# TWV.net
KiCad netlist of a schematic drawn in EAGLE
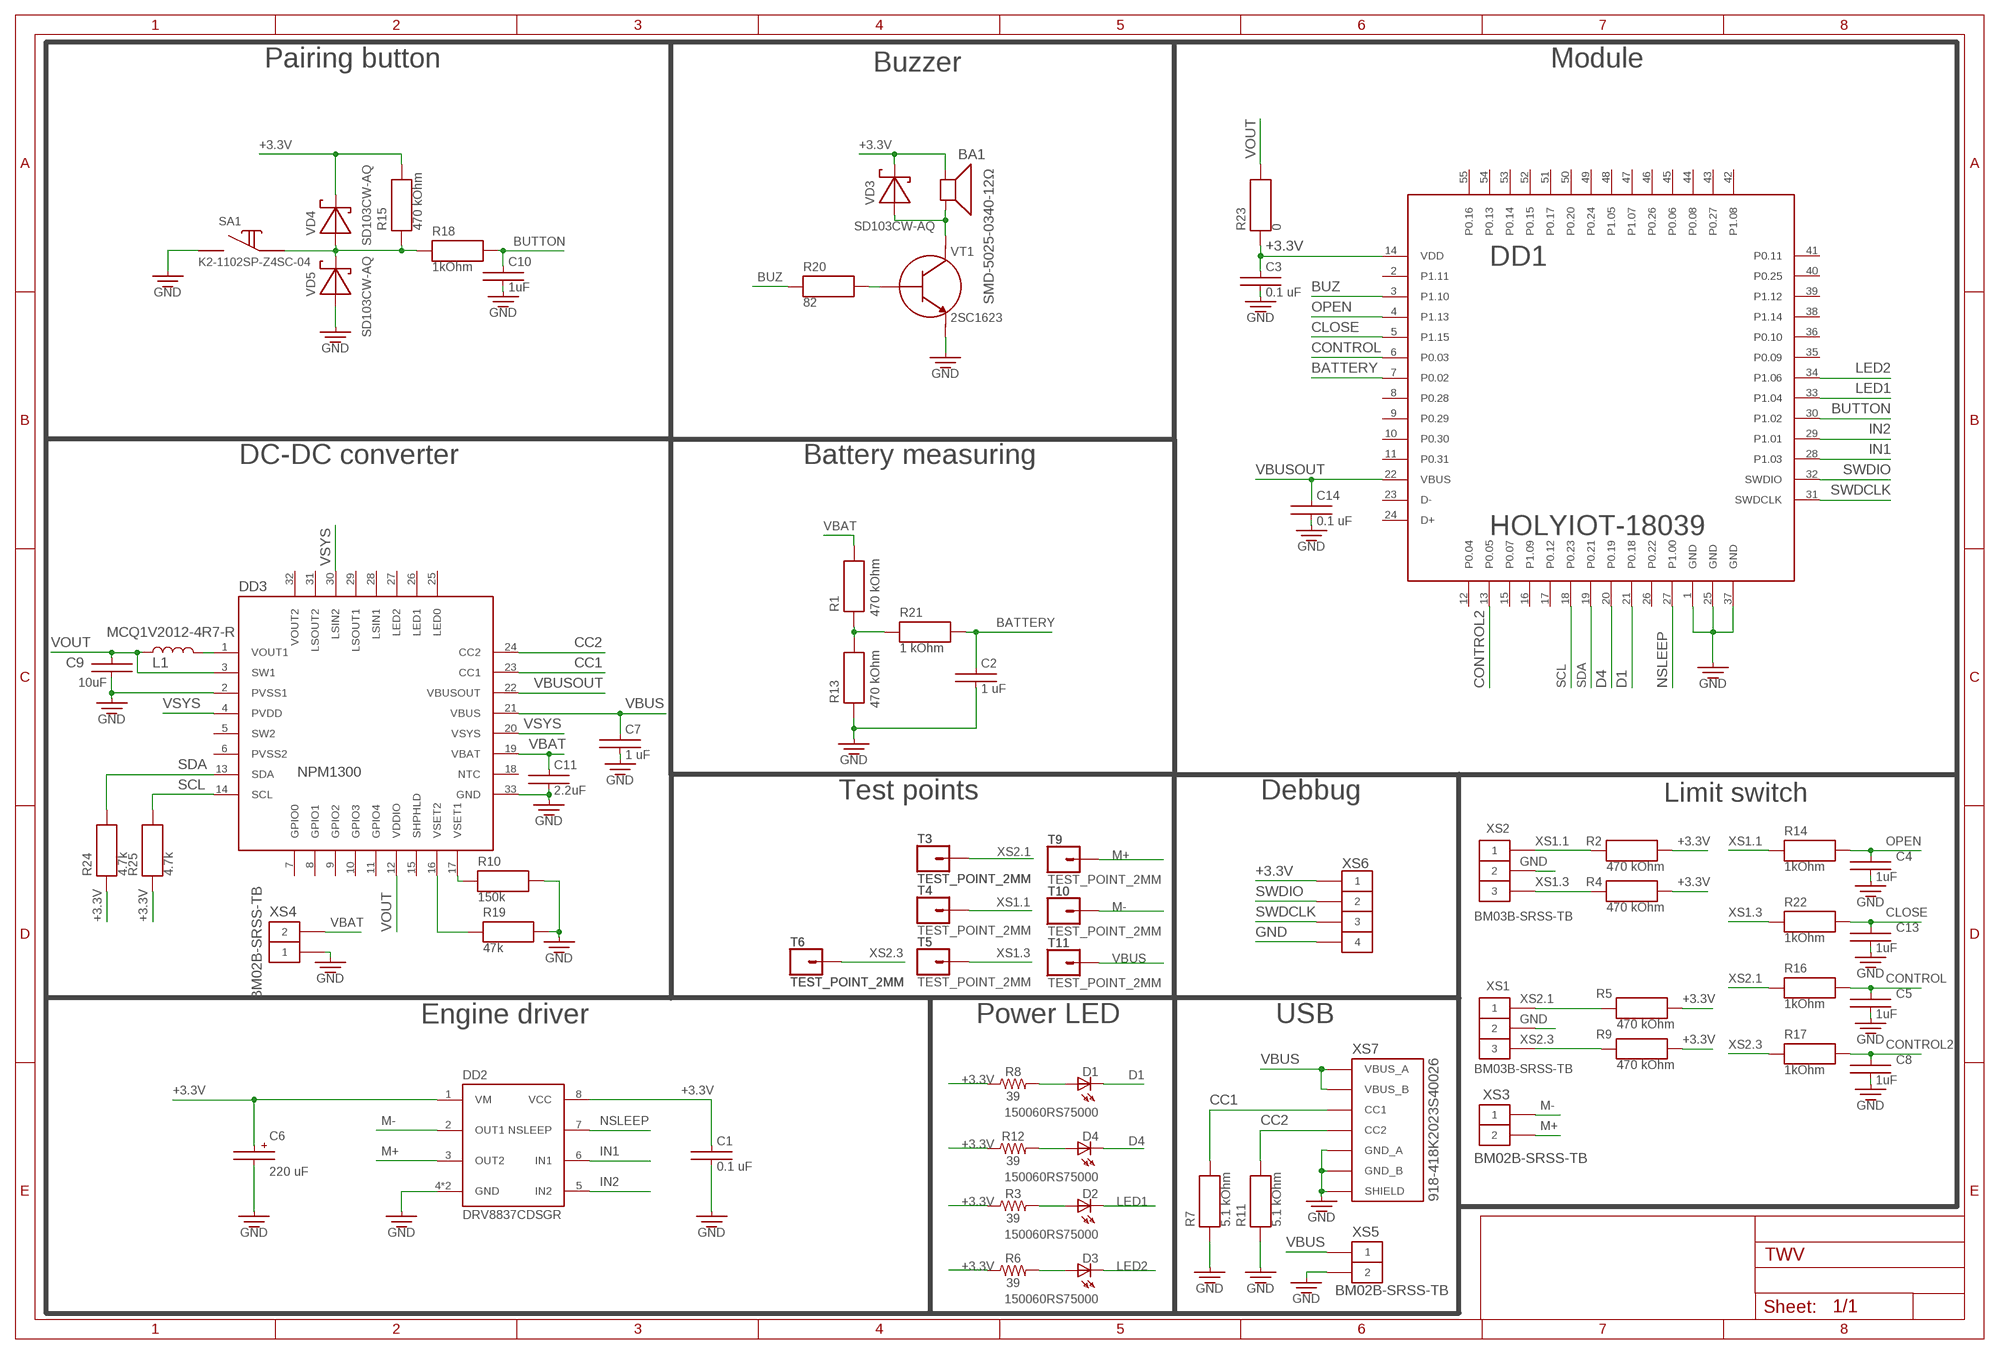
[diagram p0: schematic, sheet 1]

(export (version "E")
  (design (tool "Eeschema 10.0.6"))
  (components
    (comp (ref "BA1")
      (value "SMD-5025-0340-12Ω")
      (footprint "eagle-import:SMD-5025-0340-12Ω")
      (libsource (lib "eagle-import") (part "SMD-5025-0340-12Ω"))
    )
    (comp (ref "C1")
      (value "0.1 uF")
      (footprint "eagle-import:0603")
      (libsource (lib "eagle-import") (part "CAPACITOR-0603"))
    )
    (comp (ref "C2")
      (value "1 uF")
      (footprint "eagle-import:0603")
      (libsource (lib "eagle-import") (part "CAPACITOR-0603"))
    )
    (comp (ref "C3")
      (value "0.1 uF")
      (footprint "eagle-import:0603")
      (libsource (lib "eagle-import") (part "CAPACITOR-0603"))
    )
    (comp (ref "C4")
      (value "1uF")
      (footprint "eagle-import:0603")
      (libsource (lib "eagle-import") (part "CAPACITOR-0603"))
    )
    (comp (ref "C5")
      (value "1uF")
      (footprint "eagle-import:0603")
      (libsource (lib "eagle-import") (part "CAPACITOR-0603"))
    )
    (comp (ref "C6")
      (value "220 uF")
      (footprint "eagle-import:6.3X8")
      (libsource (lib "eagle-import") (part "ALUM_CAP_SMD-6.3X8"))
    )
    (comp (ref "C7")
      (value "1 uF")
      (footprint "eagle-import:0603")
      (libsource (lib "eagle-import") (part "CAPACITOR-0603"))
    )
    (comp (ref "C8")
      (value "1uF")
      (footprint "eagle-import:0603")
      (libsource (lib "eagle-import") (part "CAPACITOR-0603"))
    )
    (comp (ref "C9")
      (value "10uF")
      (footprint "eagle-import:0603")
      (libsource (lib "eagle-import") (part "CAPACITOR-0603"))
    )
    (comp (ref "C10")
      (value "1uF")
      (footprint "eagle-import:0603")
      (libsource (lib "eagle-import") (part "CAPACITOR-0603"))
    )
    (comp (ref "C11")
      (value "2.2uF")
      (footprint "eagle-import:0603")
      (libsource (lib "eagle-import") (part "CAPACITOR-0603"))
    )
    (comp (ref "C13")
      (value "1uF")
      (footprint "eagle-import:0603")
      (libsource (lib "eagle-import") (part "CAPACITOR-0603"))
    )
    (comp (ref "C14")
      (value "0.1 uF")
      (footprint "eagle-import:0603")
      (libsource (lib "eagle-import") (part "CAPACITOR-0603"))
    )
    (comp (ref "D1")
      (value "150060RS75000")
      (footprint "eagle-import:0603")
      (fields (field (name "MANUFACTURER") "Würth Elektronik"))
      (libsource (lib "eagle-import") (part "150060RS75000"))
    )
    (comp (ref "D2")
      (value "150060RS75000")
      (footprint "eagle-import:0603")
      (fields (field (name "MANUFACTURER") "Würth Elektronik"))
      (libsource (lib "eagle-import") (part "150060RS75000"))
    )
    (comp (ref "D3")
      (value "150060RS75000")
      (footprint "eagle-import:0603")
      (fields (field (name "MANUFACTURER") "Würth Elektronik"))
      (libsource (lib "eagle-import") (part "150060RS75000"))
    )
    (comp (ref "D4")
      (value "150060RS75000")
      (footprint "eagle-import:0603")
      (fields (field (name "MANUFACTURER") "Würth Elektronik"))
      (libsource (lib "eagle-import") (part "150060RS75000"))
    )
    (comp (ref "DD1")
      (value "HOLYIOT-18039")
      (footprint "eagle-import:HOLYIOT-18039")
      (libsource (lib "eagle-import") (part "HOLYIOT-18039"))
    )
    (comp (ref "DD2")
      (value "DRV8837CDSGR")
      (footprint "eagle-import:WSON-8")
      (libsource (lib "eagle-import") (part "DRV8837CDSGR"))
    )
    (comp (ref "DD3")
      (value "NPM1300")
      (footprint "eagle-import:QFN32-5X5MM")
      (libsource (lib "eagle-import") (part "NPM1300"))
    )
    (comp (ref "L1")
      (value "MCQ1V2012-4R7-R")
      (footprint "eagle-import:0805")
      (libsource (lib "eagle-import") (part "MCQ1V2012-4R7-R"))
    )
    (comp (ref "R1")
      (value "470 kOhm")
      (footprint "eagle-import:0603")
      (libsource (lib "eagle-import") (part "RESISTOR-0603"))
    )
    (comp (ref "R2")
      (value "470 kOhm")
      (footprint "eagle-import:0603")
      (libsource (lib "eagle-import") (part "RESISTOR-0603"))
    )
    (comp (ref "R3")
      (value "39")
      (footprint "eagle-import:RES0603")
      (fields (field (name "MANUFACTURER") "Yageo") (field (name "MPN") "RC0603JR-0739RL"))
      (libsource (lib "eagle-import") (part "RC0603JR-0739RL"))
    )
    (comp (ref "R4")
      (value "470 kOhm")
      (footprint "eagle-import:0603")
      (libsource (lib "eagle-import") (part "RESISTOR-0603"))
    )
    (comp (ref "R5")
      (value "470 kOhm")
      (footprint "eagle-import:0603")
      (libsource (lib "eagle-import") (part "RESISTOR-0603"))
    )
    (comp (ref "R6")
      (value "39")
      (footprint "eagle-import:RES0603")
      (fields (field (name "MANUFACTURER") "Yageo") (field (name "MPN") "RC0603JR-0739RL"))
      (libsource (lib "eagle-import") (part "RC0603JR-0739RL"))
    )
    (comp (ref "R7")
      (value "5.1 kOhm")
      (footprint "eagle-import:0603")
      (libsource (lib "eagle-import") (part "RESISTOR-0603"))
    )
    (comp (ref "R8")
      (value "39")
      (footprint "eagle-import:RES0603")
      (fields (field (name "MANUFACTURER") "Yageo") (field (name "MPN") "RC0603JR-0739RL"))
      (libsource (lib "eagle-import") (part "RC0603JR-0739RL"))
    )
    (comp (ref "R9")
      (value "470 kOhm")
      (footprint "eagle-import:0603")
      (libsource (lib "eagle-import") (part "RESISTOR-0603"))
    )
    (comp (ref "R10")
      (value "150k")
      (footprint "eagle-import:0603")
      (libsource (lib "eagle-import") (part "RESISTOR-0603"))
    )
    (comp (ref "R11")
      (value "5.1 kOhm")
      (footprint "eagle-import:0603")
      (libsource (lib "eagle-import") (part "RESISTOR-0603"))
    )
    (comp (ref "R12")
      (value "39")
      (footprint "eagle-import:RES0603")
      (fields (field (name "MANUFACTURER") "Yageo") (field (name "MPN") "RC0603JR-0739RL"))
      (libsource (lib "eagle-import") (part "RC0603JR-0739RL"))
    )
    (comp (ref "R13")
      (value "470 kOhm")
      (footprint "eagle-import:0603")
      (libsource (lib "eagle-import") (part "RESISTOR-0603"))
    )
    (comp (ref "R14")
      (value "1kOhm")
      (footprint "eagle-import:0603")
      (libsource (lib "eagle-import") (part "RESISTOR-0603"))
    )
    (comp (ref "R15")
      (value "470 kOhm")
      (footprint "eagle-import:0603")
      (libsource (lib "eagle-import") (part "RESISTOR-0603"))
    )
    (comp (ref "R16")
      (value "1kOhm")
      (footprint "eagle-import:0603")
      (libsource (lib "eagle-import") (part "RESISTOR-0603"))
    )
    (comp (ref "R17")
      (value "1kOhm")
      (footprint "eagle-import:0603")
      (libsource (lib "eagle-import") (part "RESISTOR-0603"))
    )
    (comp (ref "R18")
      (value "1kOhm")
      (footprint "eagle-import:0603")
      (libsource (lib "eagle-import") (part "RESISTOR-0603"))
    )
    (comp (ref "R19")
      (value "47k")
      (footprint "eagle-import:0603")
      (libsource (lib "eagle-import") (part "RESISTOR-0603"))
    )
    (comp (ref "R20")
      (value "82")
      (footprint "eagle-import:0603")
      (libsource (lib "eagle-import") (part "RESISTOR-0603"))
    )
    (comp (ref "R21")
      (value "1 kOhm")
      (footprint "eagle-import:0603")
      (libsource (lib "eagle-import") (part "RESISTOR-0603"))
    )
    (comp (ref "R22")
      (value "1kOhm")
      (footprint "eagle-import:0603")
      (libsource (lib "eagle-import") (part "RESISTOR-0603"))
    )
    (comp (ref "R23")
      (value "0")
      (footprint "eagle-import:0805")
      (libsource (lib "eagle-import") (part "RESISTOR-0805"))
    )
    (comp (ref "R24")
      (value "4.7k")
      (footprint "eagle-import:0603")
      (libsource (lib "eagle-import") (part "RESISTOR-0603"))
    )
    (comp (ref "R25")
      (value "4.7k")
      (footprint "eagle-import:0603")
      (libsource (lib "eagle-import") (part "RESISTOR-0603"))
    )
    (comp (ref "SA1")
      (value "K2-1102SP-Z4SC-04")
      (footprint "eagle-import:K2-1102SP-Z4SC-04")
      (libsource (lib "eagle-import") (part "K2-1102SP-Z4SC-04"))
    )
    (comp (ref "T3")
      (value "TEST_POINT_2MM")
      (footprint "eagle-import:TEST_POINT_2MM")
      (libsource (lib "eagle-import") (part "TEST_POINT_2MM"))
    )
    (comp (ref "T4")
      (value "TEST_POINT_2MM")
      (footprint "eagle-import:TEST_POINT_2MM")
      (libsource (lib "eagle-import") (part "TEST_POINT_2MM"))
    )
    (comp (ref "T5")
      (value "TEST_POINT_2MM")
      (footprint "eagle-import:TEST_POINT_2MM")
      (libsource (lib "eagle-import") (part "TEST_POINT_2MM"))
    )
    (comp (ref "T6")
      (value "TEST_POINT_2MM")
      (footprint "eagle-import:TEST_POINT_2MM")
      (libsource (lib "eagle-import") (part "TEST_POINT_2MM"))
    )
    (comp (ref "T9")
      (value "TEST_POINT_2MM")
      (footprint "eagle-import:TEST_POINT_2MM")
      (libsource (lib "eagle-import") (part "TEST_POINT_2MM"))
    )
    (comp (ref "T10")
      (value "TEST_POINT_2MM")
      (footprint "eagle-import:TEST_POINT_2MM")
      (libsource (lib "eagle-import") (part "TEST_POINT_2MM"))
    )
    (comp (ref "T11")
      (value "TEST_POINT_2MM")
      (footprint "eagle-import:TEST_POINT_2MM")
      (libsource (lib "eagle-import") (part "TEST_POINT_2MM"))
    )
    (comp (ref "VD3")
      (value "SD103CW-AQ")
      (footprint "eagle-import:SOD-123F")
      (libsource (lib "eagle-import") (part "SD103CW-AQ"))
    )
    (comp (ref "VD4")
      (value "SD103CW-AQ")
      (footprint "eagle-import:SOD-123F")
      (libsource (lib "eagle-import") (part "SD103CW-AQ"))
    )
    (comp (ref "VD5")
      (value "SD103CW-AQ")
      (footprint "eagle-import:SOD-123F")
      (libsource (lib "eagle-import") (part "SD103CW-AQ"))
    )
    (comp (ref "VT1")
      (value "2SC1623")
      (footprint "eagle-import:SOT-23")
      (libsource (lib "eagle-import") (part "2SC1623"))
    )
    (comp (ref "XS1")
      (value "BM03B-SRSS-TB")
      (footprint "eagle-import:BM03B-SRSS-TB")
      (libsource (lib "eagle-import") (part "BM03B-SRSS-TB"))
    )
    (comp (ref "XS2")
      (value "BM03B-SRSS-TB")
      (footprint "eagle-import:BM03B-SRSS-TB")
      (libsource (lib "eagle-import") (part "BM03B-SRSS-TB"))
    )
    (comp (ref "XS3")
      (value "BM02B-SRSS-TB")
      (footprint "eagle-import:BM02B-SRSS-TB")
      (libsource (lib "eagle-import") (part "BM02B-SRSS-TB"))
    )
    (comp (ref "XS4")
      (value "BM02B-SRSS-TB")
      (footprint "eagle-import:BM02B-SRSS-TB")
      (libsource (lib "eagle-import") (part "BM02B-SRSS-TB"))
    )
    (comp (ref "XS5")
      (value "BM02B-SRSS-TB")
      (footprint "eagle-import:BM02B-SRSS-TB")
      (libsource (lib "eagle-import") (part "BM02B-SRSS-TB"))
    )
    (comp (ref "XS6")
      (value "TH1X4-2.54MM")
      (footprint "eagle-import:TH1X4-2.54MM")
      (libsource (lib "eagle-import") (part "TH1X4-2.54MM"))
    )
    (comp (ref "XS7")
      (value "918-418K2023S40026")
      (footprint "eagle-import:918-418K2023S40026")
      (libsource (lib "eagle-import") (part "918-418K2023S40026"))
    )
  )
  (nets
    (net (code "1") (name "/+3.3V") (class "Default")
      (node (ref "BA1") (pin "+") (pinfunction "+_+") (pintype "bidirectional"))
      (node (ref "C1") (pin "1") (pinfunction "1_1") (pintype "bidirectional"))
      (node (ref "C3") (pin "1") (pinfunction "1_1") (pintype "bidirectional"))
      (node (ref "C6") (pin "+") (pinfunction "+_+") (pintype "bidirectional"))
      (node (ref "DD1") (pin "14") (pinfunction "VDD_14") (pintype "bidirectional"))
      (node (ref "DD2") (pin "1") (pinfunction "VM_1") (pintype "bidirectional"))
      (node (ref "DD2") (pin "8") (pinfunction "VCC_8") (pintype "bidirectional"))
      (node (ref "R12") (pin "1") (pinfunction "1_1") (pintype "passive"))
      (node (ref "R15") (pin "2") (pinfunction "2_2") (pintype "bidirectional"))
      (node (ref "R2") (pin "2") (pinfunction "2_2") (pintype "bidirectional"))
      (node (ref "R23") (pin "1") (pinfunction "1_1") (pintype "bidirectional"))
      (node (ref "R24") (pin "1") (pinfunction "1_1") (pintype "bidirectional"))
      (node (ref "R25") (pin "1") (pinfunction "1_1") (pintype "bidirectional"))
      (node (ref "R3") (pin "1") (pinfunction "1_1") (pintype "passive"))
      (node (ref "R4") (pin "2") (pinfunction "2_2") (pintype "bidirectional"))
      (node (ref "R5") (pin "2") (pinfunction "2_2") (pintype "bidirectional"))
      (node (ref "R6") (pin "1") (pinfunction "1_1") (pintype "passive"))
      (node (ref "R8") (pin "1") (pinfunction "1_1") (pintype "passive"))
      (node (ref "R9") (pin "2") (pinfunction "2_2") (pintype "bidirectional"))
      (node (ref "VD3") (pin "C") (pinfunction "C_C") (pintype "bidirectional"))
      (node (ref "VD4") (pin "C") (pinfunction "C_C") (pintype "bidirectional"))
      (node (ref "XS6") (pin "1") (pinfunction "1_1") (pintype "bidirectional"))
    )
    (net (code "2") (name "/BATTERY") (class "Default")
      (node (ref "C2") (pin "1") (pinfunction "1_1") (pintype "bidirectional"))
      (node (ref "DD1") (pin "7") (pinfunction "P0.02_7") (pintype "bidirectional"))
      (node (ref "R21") (pin "2") (pinfunction "2_2") (pintype "bidirectional"))
    )
    (net (code "3") (name "/BUTTON") (class "Default")
      (node (ref "C10") (pin "1") (pinfunction "1_1") (pintype "bidirectional"))
      (node (ref "DD1") (pin "30") (pinfunction "P1.02_30") (pintype "bidirectional"))
      (node (ref "R18") (pin "2") (pinfunction "2_2") (pintype "bidirectional"))
    )
    (net (code "4") (name "/BUZ") (class "Default")
      (node (ref "DD1") (pin "3") (pinfunction "P1.10_3") (pintype "bidirectional"))
      (node (ref "R20") (pin "1") (pinfunction "1_1") (pintype "bidirectional"))
    )
    (net (code "5") (name "/CC1") (class "Default")
      (node (ref "DD3") (pin "23") (pinfunction "CC1_23") (pintype "bidirectional"))
      (node (ref "R7") (pin "2") (pinfunction "2_2") (pintype "bidirectional"))
      (node (ref "XS7") (pin "A5") (pinfunction "CC1_A5") (pintype "bidirectional"))
    )
    (net (code "6") (name "/CC2") (class "Default")
      (node (ref "DD3") (pin "24") (pinfunction "CC2_24") (pintype "bidirectional"))
      (node (ref "R11") (pin "2") (pinfunction "2_2") (pintype "bidirectional"))
      (node (ref "XS7") (pin "B5") (pinfunction "CC2_B5") (pintype "bidirectional"))
    )
    (net (code "7") (name "/CLOSE") (class "Default")
      (node (ref "C13") (pin "1") (pinfunction "1_1") (pintype "bidirectional"))
      (node (ref "DD1") (pin "5") (pinfunction "P1.15_5") (pintype "bidirectional"))
      (node (ref "R22") (pin "2") (pinfunction "2_2") (pintype "bidirectional"))
    )
    (net (code "8") (name "/CONTROL") (class "Default")
      (node (ref "C5") (pin "1") (pinfunction "1_1") (pintype "bidirectional"))
      (node (ref "DD1") (pin "6") (pinfunction "P0.03_6") (pintype "bidirectional"))
      (node (ref "R16") (pin "2") (pinfunction "2_2") (pintype "bidirectional"))
    )
    (net (code "9") (name "/CONTROL2") (class "Default")
      (node (ref "C8") (pin "1") (pinfunction "1_1") (pintype "bidirectional"))
      (node (ref "DD1") (pin "13") (pinfunction "P0.05_13") (pintype "bidirectional"))
      (node (ref "R17") (pin "2") (pinfunction "2_2") (pintype "bidirectional"))
    )
    (net (code "10") (name "/D1") (class "Default")
      (node (ref "D1") (pin "C") (pinfunction "K_C") (pintype "passive"))
      (node (ref "DD1") (pin "21") (pinfunction "P0.18_21") (pintype "bidirectional"))
    )
    (net (code "11") (name "/D4") (class "Default")
      (node (ref "D4") (pin "C") (pinfunction "K_C") (pintype "passive"))
      (node (ref "DD1") (pin "20") (pinfunction "P0.19_20") (pintype "bidirectional"))
    )
    (net (code "12") (name "/IN1") (class "Default")
      (node (ref "DD1") (pin "28") (pinfunction "P1.03_28") (pintype "bidirectional"))
      (node (ref "DD2") (pin "6") (pinfunction "IN1_6") (pintype "bidirectional"))
    )
    (net (code "13") (name "/IN2") (class "Default")
      (node (ref "DD1") (pin "29") (pinfunction "P1.01_29") (pintype "bidirectional"))
      (node (ref "DD2") (pin "5") (pinfunction "IN2_5") (pintype "bidirectional"))
    )
    (net (code "14") (name "/LED1") (class "Default")
      (node (ref "D2") (pin "C") (pinfunction "K_C") (pintype "passive"))
      (node (ref "DD1") (pin "33") (pinfunction "P1.04_33") (pintype "bidirectional"))
    )
    (net (code "15") (name "/LED2") (class "Default")
      (node (ref "D3") (pin "C") (pinfunction "K_C") (pintype "passive"))
      (node (ref "DD1") (pin "34") (pinfunction "P1.06_34") (pintype "bidirectional"))
    )
    (net (code "16") (name "/M+") (class "Default")
      (node (ref "DD2") (pin "3") (pinfunction "OUT2_3") (pintype "bidirectional"))
      (node (ref "T9") (pin "1") (pinfunction "1_1") (pintype "passive"))
      (node (ref "XS3") (pin "2") (pinfunction "2_2") (pintype "bidirectional"))
    )
    (net (code "17") (name "/M-") (class "Default")
      (node (ref "DD2") (pin "2") (pinfunction "OUT1_2") (pintype "bidirectional"))
      (node (ref "T10") (pin "1") (pinfunction "1_1") (pintype "passive"))
      (node (ref "XS3") (pin "1") (pinfunction "1_1") (pintype "bidirectional"))
    )
    (net (code "18") (name "/NSLEEP") (class "Default")
      (node (ref "DD1") (pin "27") (pinfunction "P1.00_27") (pintype "bidirectional"))
      (node (ref "DD2") (pin "7") (pinfunction "NSLEEP_7") (pintype "bidirectional"))
    )
    (net (code "19") (name "/OPEN") (class "Default")
      (node (ref "C4") (pin "1") (pinfunction "1_1") (pintype "bidirectional"))
      (node (ref "DD1") (pin "4") (pinfunction "P1.13_4") (pintype "bidirectional"))
      (node (ref "R14") (pin "2") (pinfunction "2_2") (pintype "bidirectional"))
    )
    (net (code "20") (name "/SCL") (class "Default")
      (node (ref "DD1") (pin "18") (pinfunction "P0.23_18") (pintype "bidirectional"))
      (node (ref "DD3") (pin "14") (pinfunction "SCL_14") (pintype "bidirectional"))
      (node (ref "R25") (pin "2") (pinfunction "2_2") (pintype "bidirectional"))
    )
    (net (code "21") (name "/SDA") (class "Default")
      (node (ref "DD1") (pin "19") (pinfunction "P0.21_19") (pintype "bidirectional"))
      (node (ref "DD3") (pin "13") (pinfunction "SDA_13") (pintype "bidirectional"))
      (node (ref "R24") (pin "2") (pinfunction "2_2") (pintype "bidirectional"))
    )
    (net (code "22") (name "/SWDCLK") (class "Default")
      (node (ref "DD1") (pin "31") (pinfunction "SWDCLK_31") (pintype "bidirectional"))
      (node (ref "XS6") (pin "3") (pinfunction "3_3") (pintype "bidirectional"))
    )
    (net (code "23") (name "/SWDIO") (class "Default")
      (node (ref "DD1") (pin "32") (pinfunction "SWDIO_32") (pintype "bidirectional"))
      (node (ref "XS6") (pin "2") (pinfunction "2_2") (pintype "bidirectional"))
    )
    (net (code "24") (name "/VBAT") (class "Default")
      (node (ref "C11") (pin "1") (pinfunction "1_1") (pintype "bidirectional"))
      (node (ref "DD3") (pin "19") (pinfunction "VBAT_19") (pintype "bidirectional"))
      (node (ref "R1") (pin "2") (pinfunction "2_2") (pintype "bidirectional"))
      (node (ref "XS4") (pin "2") (pinfunction "2_2") (pintype "bidirectional"))
    )
    (net (code "25") (name "/VBUS") (class "Default")
      (node (ref "C7") (pin "1") (pinfunction "1_1") (pintype "bidirectional"))
      (node (ref "DD3") (pin "21") (pinfunction "VBUS_21") (pintype "bidirectional"))
      (node (ref "T11") (pin "1") (pinfunction "1_1") (pintype "passive"))
      (node (ref "XS5") (pin "1") (pinfunction "1_1") (pintype "bidirectional"))
      (node (ref "XS7") (pin "A9") (pinfunction "VBUS_A_A9") (pintype "bidirectional"))
      (node (ref "XS7") (pin "B9") (pinfunction "VBUS_B_B9") (pintype "bidirectional"))
    )
    (net (code "26") (name "/VBUSOUT") (class "Default")
      (node (ref "C14") (pin "1") (pinfunction "1_1") (pintype "bidirectional"))
      (node (ref "DD1") (pin "22") (pinfunction "VBUS_22") (pintype "bidirectional"))
      (node (ref "DD3") (pin "22") (pinfunction "VBUSOUT_22") (pintype "bidirectional"))
    )
    (net (code "27") (name "/VOUT") (class "Default")
      (node (ref "C9") (pin "1") (pinfunction "1_1") (pintype "bidirectional"))
      (node (ref "DD3") (pin "12") (pinfunction "VDDIO_12") (pintype "bidirectional"))
      (node (ref "DD3") (pin "3") (pinfunction "SW1_3") (pintype "bidirectional"))
      (node (ref "L1") (pin "P$1") (pinfunction "1_P$1") (pintype "bidirectional"))
      (node (ref "R23") (pin "2") (pinfunction "2_2") (pintype "bidirectional"))
    )
    (net (code "28") (name "/VSYS") (class "Default")
      (node (ref "DD3") (pin "20") (pinfunction "VSYS_20") (pintype "bidirectional"))
      (node (ref "DD3") (pin "30") (pinfunction "LSIN2_30") (pintype "bidirectional"))
      (node (ref "DD3") (pin "4") (pinfunction "PVDD_4") (pintype "bidirectional"))
    )
    (net (code "29") (name "/XS1.1") (class "Default")
      (node (ref "R14") (pin "1") (pinfunction "1_1") (pintype "bidirectional"))
      (node (ref "R2") (pin "1") (pinfunction "1_1") (pintype "bidirectional"))
      (node (ref "T4") (pin "1") (pinfunction "1_1") (pintype "passive"))
      (node (ref "XS2") (pin "1") (pinfunction "1_1") (pintype "bidirectional"))
    )
    (net (code "30") (name "/XS1.3") (class "Default")
      (node (ref "R22") (pin "1") (pinfunction "1_1") (pintype "bidirectional"))
      (node (ref "R4") (pin "1") (pinfunction "1_1") (pintype "bidirectional"))
      (node (ref "T5") (pin "1") (pinfunction "1_1") (pintype "passive"))
      (node (ref "XS2") (pin "3") (pinfunction "3_3") (pintype "bidirectional"))
    )
    (net (code "31") (name "/XS2.1") (class "Default")
      (node (ref "R16") (pin "1") (pinfunction "1_1") (pintype "bidirectional"))
      (node (ref "R5") (pin "1") (pinfunction "1_1") (pintype "bidirectional"))
      (node (ref "T3") (pin "1") (pinfunction "1_1") (pintype "passive"))
      (node (ref "XS1") (pin "1") (pinfunction "1_1") (pintype "bidirectional"))
    )
    (net (code "32") (name "/XS2.3") (class "Default")
      (node (ref "R17") (pin "1") (pinfunction "1_1") (pintype "bidirectional"))
      (node (ref "R9") (pin "1") (pinfunction "1_1") (pintype "bidirectional"))
      (node (ref "T6") (pin "1") (pinfunction "1_1") (pintype "passive"))
      (node (ref "XS1") (pin "3") (pinfunction "3_3") (pintype "bidirectional"))
    )
    (net (code "33") (name "GND") (class "Default")
      (node (ref "C1") (pin "2") (pinfunction "2_2") (pintype "bidirectional"))
      (node (ref "C10") (pin "2") (pinfunction "2_2") (pintype "bidirectional"))
      (node (ref "C11") (pin "2") (pinfunction "2_2") (pintype "bidirectional"))
      (node (ref "C13") (pin "2") (pinfunction "2_2") (pintype "bidirectional"))
      (node (ref "C14") (pin "2") (pinfunction "2_2") (pintype "bidirectional"))
      (node (ref "C2") (pin "2") (pinfunction "2_2") (pintype "bidirectional"))
      (node (ref "C3") (pin "2") (pinfunction "2_2") (pintype "bidirectional"))
      (node (ref "C4") (pin "2") (pinfunction "2_2") (pintype "bidirectional"))
      (node (ref "C5") (pin "2") (pinfunction "2_2") (pintype "bidirectional"))
      (node (ref "C6") (pin "-") (pinfunction "-_-") (pintype "bidirectional"))
      (node (ref "C7") (pin "2") (pinfunction "2_2") (pintype "bidirectional"))
      (node (ref "C8") (pin "2") (pinfunction "2_2") (pintype "bidirectional"))
      (node (ref "C9") (pin "2") (pinfunction "2_2") (pintype "bidirectional"))
      (node (ref "DD1") (pin "1") (pinfunction "GND_1") (pintype "bidirectional"))
      (node (ref "DD1") (pin "25") (pinfunction "GND_25") (pintype "bidirectional"))
      (node (ref "DD1") (pin "37") (pinfunction "GND_37") (pintype "bidirectional"))
      (node (ref "DD2") (pin "4") (pinfunction "GND_4") (pintype "bidirectional"))
      (node (ref "DD2") (pin "GND") (pinfunction "GND_GND") (pintype "bidirectional"))
      (node (ref "DD3") (pin "2") (pinfunction "PVSS1_2") (pintype "bidirectional"))
      (node (ref "DD3") (pin "33") (pinfunction "GND_33") (pintype "bidirectional"))
      (node (ref "R10") (pin "2") (pinfunction "2_2") (pintype "bidirectional"))
      (node (ref "R11") (pin "1") (pinfunction "1_1") (pintype "bidirectional"))
      (node (ref "R13") (pin "1") (pinfunction "1_1") (pintype "bidirectional"))
      (node (ref "R19") (pin "2") (pinfunction "2_2") (pintype "bidirectional"))
      (node (ref "R7") (pin "1") (pinfunction "1_1") (pintype "bidirectional"))
      (node (ref "SA1") (pin "1") (pinfunction "1_1") (pintype "bidirectional"))
      (node (ref "SA1") (pin "4") (pinfunction "1_4") (pintype "bidirectional"))
      (node (ref "VD5") (pin "A") (pinfunction "A_A") (pintype "bidirectional"))
      (node (ref "VT1") (pin "2") (pinfunction "E_2") (pintype "bidirectional"))
      (node (ref "XS1") (pin "2") (pinfunction "2_2") (pintype "bidirectional"))
      (node (ref "XS2") (pin "2") (pinfunction "2_2") (pintype "bidirectional"))
      (node (ref "XS4") (pin "1") (pinfunction "1_1") (pintype "bidirectional"))
      (node (ref "XS5") (pin "2") (pinfunction "2_2") (pintype "bidirectional"))
      (node (ref "XS6") (pin "4") (pinfunction "4_4") (pintype "bidirectional"))
      (node (ref "XS7") (pin "A12") (pinfunction "GND_A_A12") (pintype "bidirectional"))
      (node (ref "XS7") (pin "B12") (pinfunction "GND_B_B12") (pintype "bidirectional"))
      (node (ref "XS7") (pin "SH1") (pinfunction "SHIELD_SH1") (pintype "bidirectional"))
      (node (ref "XS7") (pin "SH2") (pinfunction "SHIELD_SH2") (pintype "bidirectional"))
      (node (ref "XS7") (pin "SH3") (pinfunction "SHIELD_SH3") (pintype "bidirectional"))
      (node (ref "XS7") (pin "SH4") (pinfunction "SHIELD_SH4") (pintype "bidirectional"))
    )
    (net (code "34") (name "Net-(D1-PadA)") (class "Default")
      (node (ref "D1") (pin "A") (pinfunction "A_A") (pintype "passive"))
      (node (ref "R8") (pin "2") (pinfunction "2_2") (pintype "passive"))
    )
    (net (code "35") (name "Net-(D2-PadA)") (class "Default")
      (node (ref "D2") (pin "A") (pinfunction "A_A") (pintype "passive"))
      (node (ref "R3") (pin "2") (pinfunction "2_2") (pintype "passive"))
    )
    (net (code "36") (name "Net-(D3-PadA)") (class "Default")
      (node (ref "D3") (pin "A") (pinfunction "A_A") (pintype "passive"))
      (node (ref "R6") (pin "2") (pinfunction "2_2") (pintype "passive"))
    )
    (net (code "37") (name "Net-(D4-PadA)") (class "Default")
      (node (ref "D4") (pin "A") (pinfunction "A_A") (pintype "passive"))
      (node (ref "R12") (pin "2") (pinfunction "2_2") (pintype "passive"))
    )
    (net (code "38") (name "Net-(DD3-VOUT1)") (class "Default")
      (node (ref "DD3") (pin "1") (pinfunction "VOUT1_1") (pintype "bidirectional"))
      (node (ref "L1") (pin "P$2") (pinfunction "2_P$2") (pintype "bidirectional"))
    )
    (net (code "39") (name "Net-(DD3-VSET1)") (class "Default")
      (node (ref "DD3") (pin "17") (pinfunction "VSET1_17") (pintype "bidirectional"))
      (node (ref "R10") (pin "1") (pinfunction "1_1") (pintype "bidirectional"))
    )
    (net (code "40") (name "Net-(DD3-VSET2)") (class "Default")
      (node (ref "DD3") (pin "16") (pinfunction "VSET2_16") (pintype "bidirectional"))
      (node (ref "R19") (pin "1") (pinfunction "1_1") (pintype "bidirectional"))
    )
    (net (code "41") (name "Net-(R1-Pad1)") (class "Default")
      (node (ref "R1") (pin "1") (pinfunction "1_1") (pintype "bidirectional"))
      (node (ref "R13") (pin "2") (pinfunction "2_2") (pintype "bidirectional"))
      (node (ref "R21") (pin "1") (pinfunction "1_1") (pintype "bidirectional"))
    )
    (net (code "42") (name "Net-(R15-Pad1)") (class "Default")
      (node (ref "R15") (pin "1") (pinfunction "1_1") (pintype "bidirectional"))
      (node (ref "R18") (pin "1") (pinfunction "1_1") (pintype "bidirectional"))
      (node (ref "SA1") (pin "2") (pinfunction "2_2") (pintype "bidirectional"))
      (node (ref "SA1") (pin "3") (pinfunction "2_3") (pintype "bidirectional"))
      (node (ref "VD4") (pin "A") (pinfunction "A_A") (pintype "bidirectional"))
      (node (ref "VD5") (pin "C") (pinfunction "C_C") (pintype "bidirectional"))
    )
    (net (code "43") (name "Net-(VT1-B)") (class "Default")
      (node (ref "R20") (pin "2") (pinfunction "2_2") (pintype "bidirectional"))
      (node (ref "VT1") (pin "1") (pinfunction "B_1") (pintype "bidirectional"))
    )
    (net (code "44") (name "Net-(VT1-C)") (class "Default")
      (node (ref "BA1") (pin "-") (pinfunction "-_-") (pintype "bidirectional"))
      (node (ref "VD3") (pin "A") (pinfunction "A_A") (pintype "bidirectional"))
      (node (ref "VT1") (pin "3") (pinfunction "C_3") (pintype "bidirectional"))
    )
    (net (code "45") (name "unconnected-(DD1-D+-Pad24)") (class "Default")
      (node (ref "DD1") (pin "24") (pinfunction "D+_24") (pintype "bidirectional"))
    )
    (net (code "46") (name "unconnected-(DD1-D--Pad23)") (class "Default")
      (node (ref "DD1") (pin "23") (pinfunction "D-_23") (pintype "bidirectional"))
    )
    (net (code "47") (name "unconnected-(DD1-P0.04-Pad12)") (class "Default")
      (node (ref "DD1") (pin "12") (pinfunction "P0.04_12") (pintype "bidirectional"))
    )
    (net (code "48") (name "unconnected-(DD1-P0.06-Pad45)") (class "Default")
      (node (ref "DD1") (pin "45") (pinfunction "P0.06_45") (pintype "bidirectional"))
    )
    (net (code "49") (name "unconnected-(DD1-P0.07-Pad15)") (class "Default")
      (node (ref "DD1") (pin "15") (pinfunction "P0.07_15") (pintype "bidirectional"))
    )
    (net (code "50") (name "unconnected-(DD1-P0.08-Pad44)") (class "Default")
      (node (ref "DD1") (pin "44") (pinfunction "P0.08_44") (pintype "bidirectional"))
    )
    (net (code "51") (name "unconnected-(DD1-P0.09-Pad35)") (class "Default")
      (node (ref "DD1") (pin "35") (pinfunction "P0.09_35") (pintype "bidirectional"))
    )
    (net (code "52") (name "unconnected-(DD1-P0.10-Pad36)") (class "Default")
      (node (ref "DD1") (pin "36") (pinfunction "P0.10_36") (pintype "bidirectional"))
    )
    (net (code "53") (name "unconnected-(DD1-P0.11-Pad41)") (class "Default")
      (node (ref "DD1") (pin "41") (pinfunction "P0.11_41") (pintype "bidirectional"))
    )
    (net (code "54") (name "unconnected-(DD1-P0.12-Pad17)") (class "Default")
      (node (ref "DD1") (pin "17") (pinfunction "P0.12_17") (pintype "bidirectional"))
    )
    (net (code "55") (name "unconnected-(DD1-P0.13-Pad54)") (class "Default")
      (node (ref "DD1") (pin "54") (pinfunction "P0.13_54") (pintype "bidirectional"))
    )
    (net (code "56") (name "unconnected-(DD1-P0.14-Pad53)") (class "Default")
      (node (ref "DD1") (pin "53") (pinfunction "P0.14_53") (pintype "bidirectional"))
    )
    (net (code "57") (name "unconnected-(DD1-P0.15-Pad52)") (class "Default")
      (node (ref "DD1") (pin "52") (pinfunction "P0.15_52") (pintype "bidirectional"))
    )
    (net (code "58") (name "unconnected-(DD1-P0.16-Pad55)") (class "Default")
      (node (ref "DD1") (pin "55") (pinfunction "P0.16_55") (pintype "bidirectional"))
    )
    (net (code "59") (name "unconnected-(DD1-P0.17-Pad51)") (class "Default")
      (node (ref "DD1") (pin "51") (pinfunction "P0.17_51") (pintype "bidirectional"))
    )
    (net (code "60") (name "unconnected-(DD1-P0.20-Pad50)") (class "Default")
      (node (ref "DD1") (pin "50") (pinfunction "P0.20_50") (pintype "bidirectional"))
    )
    (net (code "61") (name "unconnected-(DD1-P0.22-Pad26)") (class "Default")
      (node (ref "DD1") (pin "26") (pinfunction "P0.22_26") (pintype "bidirectional"))
    )
    (net (code "62") (name "unconnected-(DD1-P0.24-Pad49)") (class "Default")
      (node (ref "DD1") (pin "49") (pinfunction "P0.24_49") (pintype "bidirectional"))
    )
    (net (code "63") (name "unconnected-(DD1-P0.25-Pad40)") (class "Default")
      (node (ref "DD1") (pin "40") (pinfunction "P0.25_40") (pintype "bidirectional"))
    )
    (net (code "64") (name "unconnected-(DD1-P0.26-Pad46)") (class "Default")
      (node (ref "DD1") (pin "46") (pinfunction "P0.26_46") (pintype "bidirectional"))
    )
    (net (code "65") (name "unconnected-(DD1-P0.27-Pad43)") (class "Default")
      (node (ref "DD1") (pin "43") (pinfunction "P0.27_43") (pintype "bidirectional"))
    )
    (net (code "66") (name "unconnected-(DD1-P0.28-Pad8)") (class "Default")
      (node (ref "DD1") (pin "8") (pinfunction "P0.28_8") (pintype "bidirectional"))
    )
    (net (code "67") (name "unconnected-(DD1-P0.29-Pad9)") (class "Default")
      (node (ref "DD1") (pin "9") (pinfunction "P0.29_9") (pintype "bidirectional"))
    )
    (net (code "68") (name "unconnected-(DD1-P0.30-Pad10)") (class "Default")
      (node (ref "DD1") (pin "10") (pinfunction "P0.30_10") (pintype "bidirectional"))
    )
    (net (code "69") (name "unconnected-(DD1-P0.31-Pad11)") (class "Default")
      (node (ref "DD1") (pin "11") (pinfunction "P0.31_11") (pintype "bidirectional"))
    )
    (net (code "70") (name "unconnected-(DD1-P1.05-Pad48)") (class "Default")
      (node (ref "DD1") (pin "48") (pinfunction "P1.05_48") (pintype "bidirectional"))
    )
    (net (code "71") (name "unconnected-(DD1-P1.07-Pad47)") (class "Default")
      (node (ref "DD1") (pin "47") (pinfunction "P1.07_47") (pintype "bidirectional"))
    )
    (net (code "72") (name "unconnected-(DD1-P1.08-Pad42)") (class "Default")
      (node (ref "DD1") (pin "42") (pinfunction "P1.08_42") (pintype "bidirectional"))
    )
    (net (code "73") (name "unconnected-(DD1-P1.09-Pad16)") (class "Default")
      (node (ref "DD1") (pin "16") (pinfunction "P1.09_16") (pintype "bidirectional"))
    )
    (net (code "74") (name "unconnected-(DD1-P1.11-Pad2)") (class "Default")
      (node (ref "DD1") (pin "2") (pinfunction "P1.11_2") (pintype "bidirectional"))
    )
    (net (code "75") (name "unconnected-(DD1-P1.12-Pad39)") (class "Default")
      (node (ref "DD1") (pin "39") (pinfunction "P1.12_39") (pintype "bidirectional"))
    )
    (net (code "76") (name "unconnected-(DD1-P1.14-Pad38)") (class "Default")
      (node (ref "DD1") (pin "38") (pinfunction "P1.14_38") (pintype "bidirectional"))
    )
    (net (code "77") (name "unconnected-(DD3-GPIO0-Pad7)") (class "Default")
      (node (ref "DD3") (pin "7") (pinfunction "GPIO0_7") (pintype "bidirectional"))
    )
    (net (code "78") (name "unconnected-(DD3-GPIO1-Pad8)") (class "Default")
      (node (ref "DD3") (pin "8") (pinfunction "GPIO1_8") (pintype "bidirectional"))
    )
    (net (code "79") (name "unconnected-(DD3-GPIO2-Pad9)") (class "Default")
      (node (ref "DD3") (pin "9") (pinfunction "GPIO2_9") (pintype "bidirectional"))
    )
    (net (code "80") (name "unconnected-(DD3-GPIO3-Pad10)") (class "Default")
      (node (ref "DD3") (pin "10") (pinfunction "GPIO3_10") (pintype "bidirectional"))
    )
    (net (code "81") (name "unconnected-(DD3-GPIO4-Pad11)") (class "Default")
      (node (ref "DD3") (pin "11") (pinfunction "GPIO4_11") (pintype "bidirectional"))
    )
    (net (code "82") (name "unconnected-(DD3-LED0-Pad25)") (class "Default")
      (node (ref "DD3") (pin "25") (pinfunction "LED0_25") (pintype "bidirectional"))
    )
    (net (code "83") (name "unconnected-(DD3-LED1-Pad26)") (class "Default")
      (node (ref "DD3") (pin "26") (pinfunction "LED1_26") (pintype "bidirectional"))
    )
    (net (code "84") (name "unconnected-(DD3-LED2-Pad27)") (class "Default")
      (node (ref "DD3") (pin "27") (pinfunction "LED2_27") (pintype "bidirectional"))
    )
    (net (code "85") (name "unconnected-(DD3-LSIN1-Pad28)") (class "Default")
      (node (ref "DD3") (pin "28") (pinfunction "LSIN1_28") (pintype "bidirectional"))
    )
    (net (code "86") (name "unconnected-(DD3-LSOUT1-Pad29)") (class "Default")
      (node (ref "DD3") (pin "29") (pinfunction "LSOUT1_29") (pintype "bidirectional"))
    )
    (net (code "87") (name "unconnected-(DD3-LSOUT2-Pad31)") (class "Default")
      (node (ref "DD3") (pin "31") (pinfunction "LSOUT2_31") (pintype "bidirectional"))
    )
    (net (code "88") (name "unconnected-(DD3-NTC-Pad18)") (class "Default")
      (node (ref "DD3") (pin "18") (pinfunction "NTC_18") (pintype "bidirectional"))
    )
    (net (code "89") (name "unconnected-(DD3-PVSS2-Pad6)") (class "Default")
      (node (ref "DD3") (pin "6") (pinfunction "PVSS2_6") (pintype "bidirectional"))
    )
    (net (code "90") (name "unconnected-(DD3-SHPHLD-Pad15)") (class "Default")
      (node (ref "DD3") (pin "15") (pinfunction "SHPHLD_15") (pintype "bidirectional"))
    )
    (net (code "91") (name "unconnected-(DD3-SW2-Pad5)") (class "Default")
      (node (ref "DD3") (pin "5") (pinfunction "SW2_5") (pintype "bidirectional"))
    )
    (net (code "92") (name "unconnected-(DD3-VOUT2-Pad32)") (class "Default")
      (node (ref "DD3") (pin "32") (pinfunction "VOUT2_32") (pintype "bidirectional"))
    )
  )
)
